# lab_1.net
KiCad netlist of a schematic drawn in EasyEDA
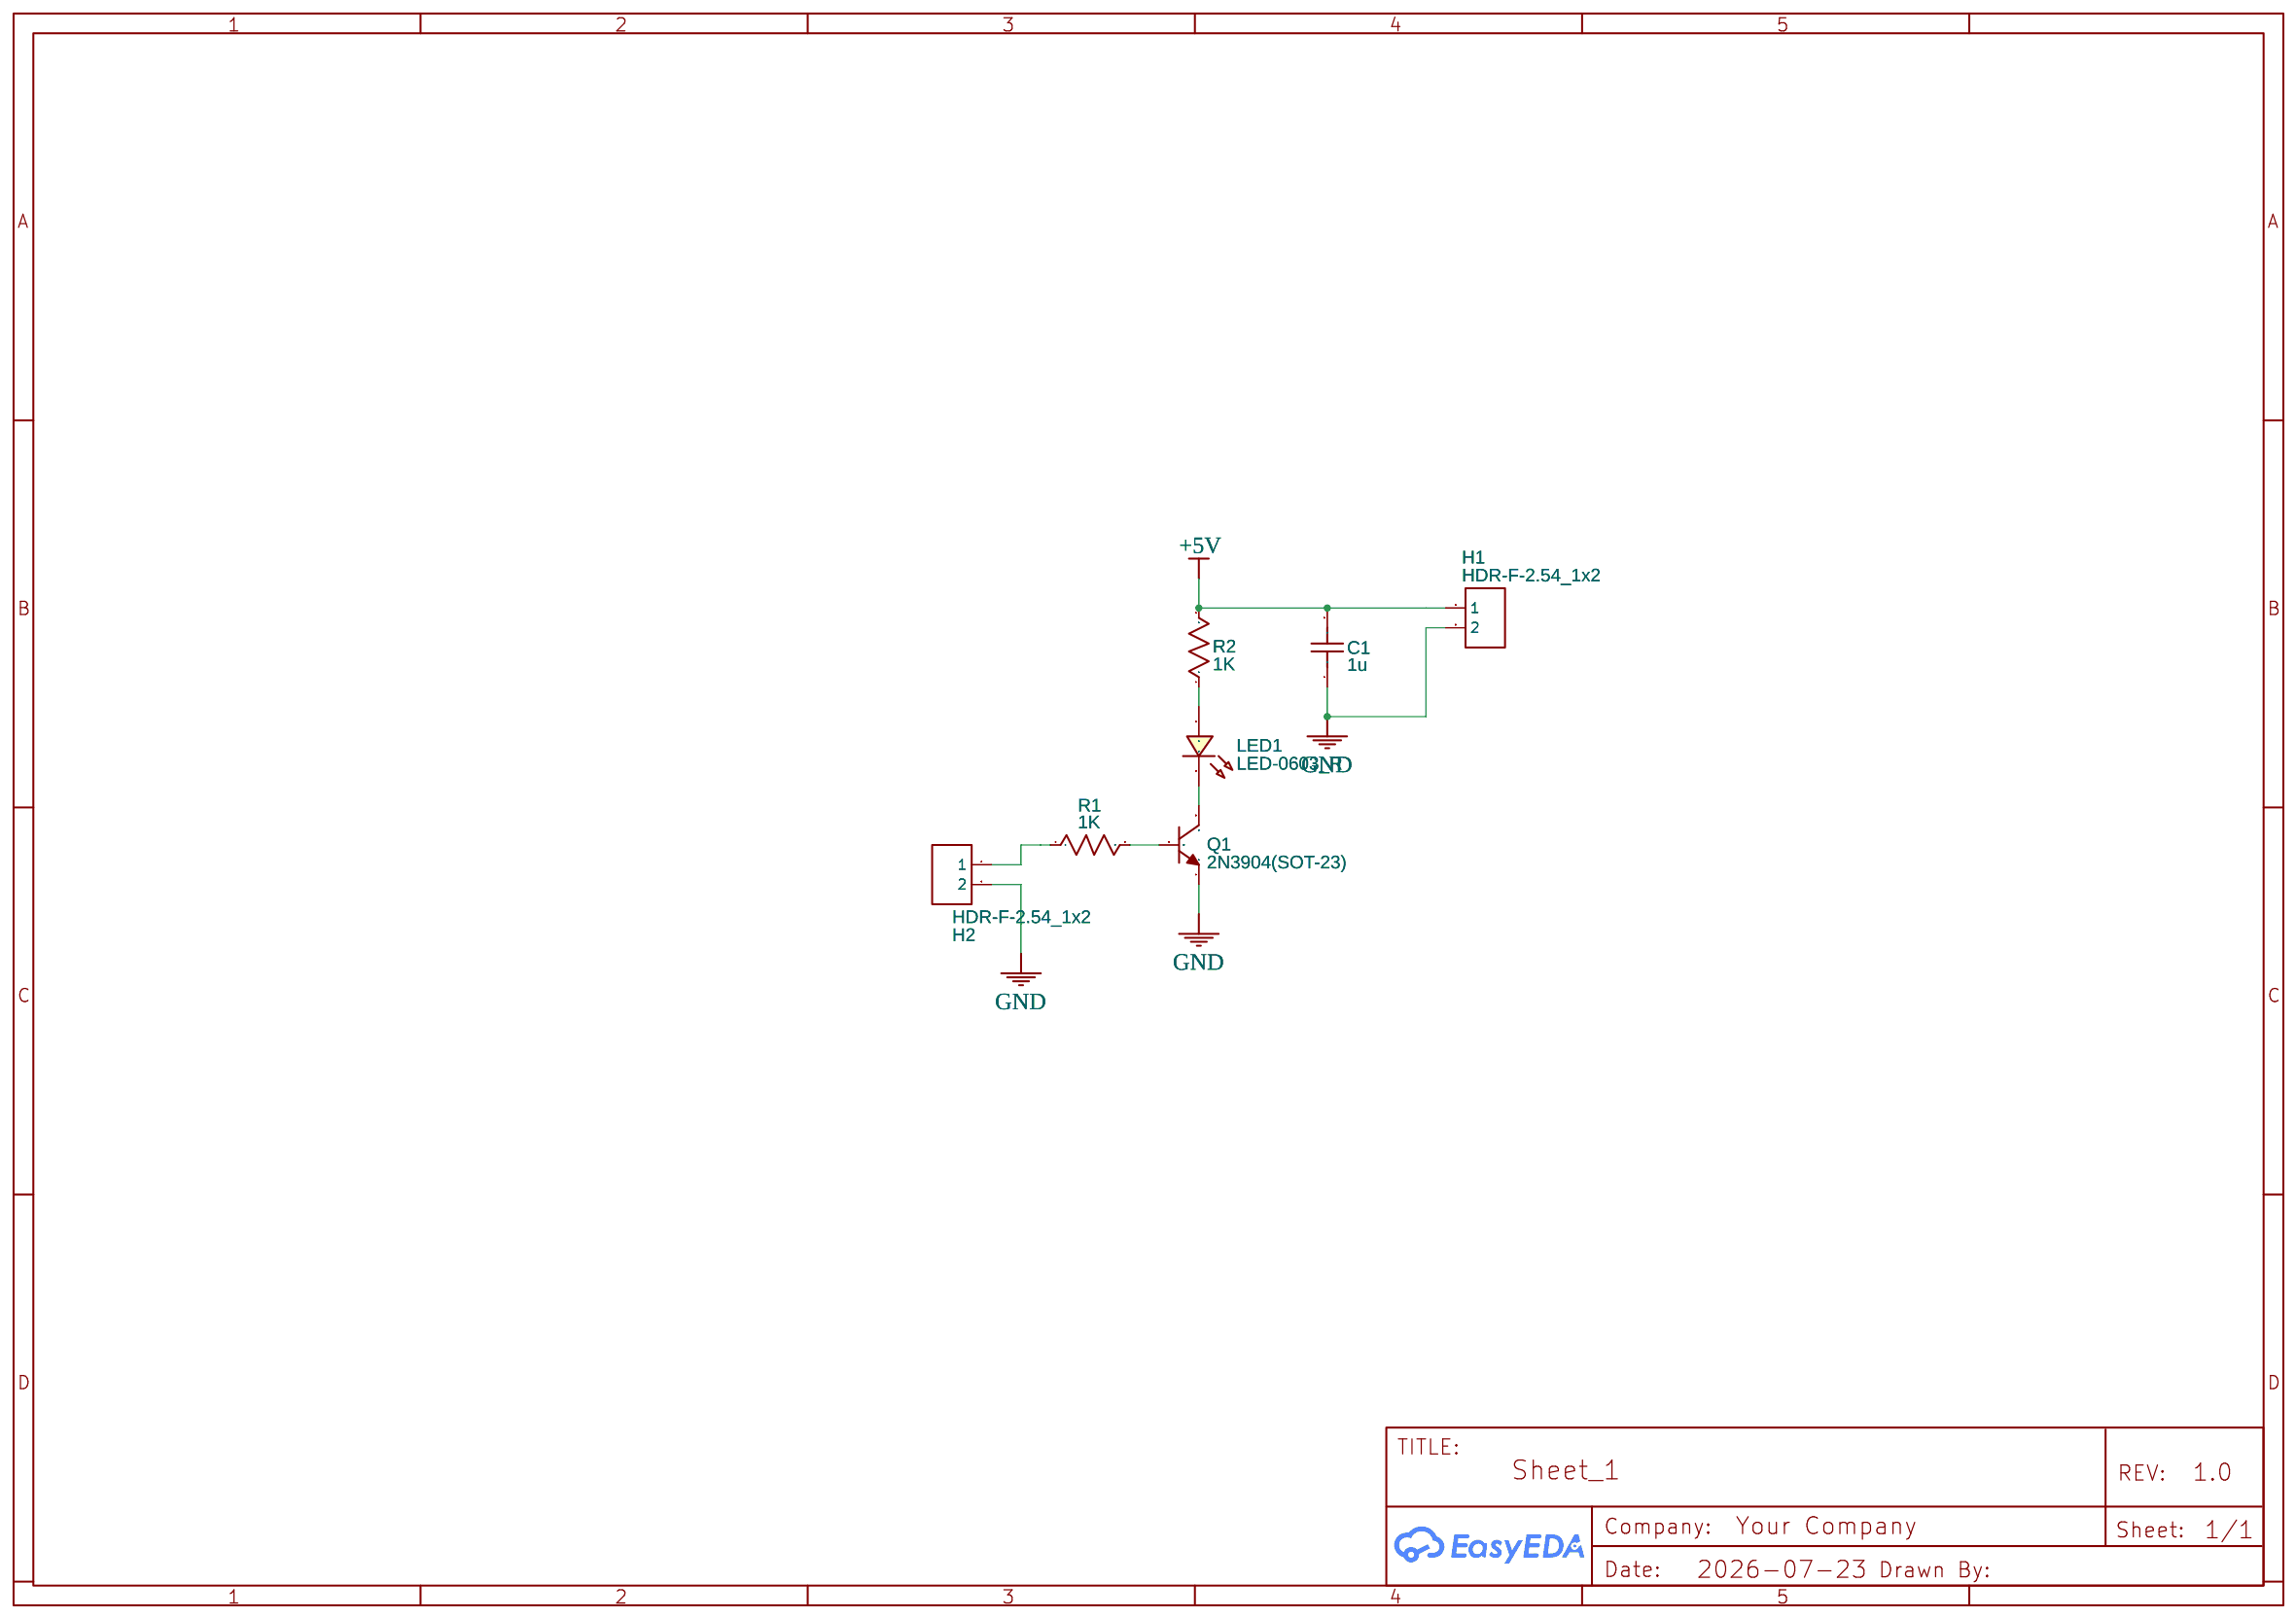
[diagram p0: schematic sheet]

(export (version "E")
  (design (tool "Eeschema 10.0.6"))
  (components
    (comp (ref "C1") (value "1u") (libsource (lib "") (part "Capacitor_US")))
    (comp (ref "H1") (value "HDR-F-2.54_1x2") (libsource (lib "") (part "HDR-F-2.54_1x2")))
    (comp (ref "H2") (value "HDR-F-2.54_1x2") (libsource (lib "") (part "HDR-F-2.54_1x2_1")))
    (comp (ref "LED1")
      (value "LED-0603_R")
      (fields
        (field (name "Manufacturer Part") "19-217/R6C-AL1M2VY/3T")
        (field (name "Manufacturer") "EVERLIGHT(台湾亿光)")
      )
      (libsource (lib "") (part "LED-0603_R"))
    )
    (comp (ref "Q1")
      (value "2N3904(SOT-23)")
      (fields (field (name "Manufacturer Part") "2n3904S-RTK/PS") (field (name "Manufacturer") "KEC"))
      (libsource (lib "") (part "2N3904(SOT-23)"))
    )
    (comp (ref "R1") (value "1K") (libsource (lib "") (part "Resistor_US")))
    (comp (ref "R2") (value "1K") (libsource (lib "") (part "Resistor_US_1")))
  )
  (nets
    (net (code "1") (name "+5V") (class "Default")
      (node (ref "C1") (pin "2") (pinfunction "2_2") (pintype "unspecified"))
      (node (ref "H1") (pin "1") (pinfunction "1_1") (pintype "input"))
      (node (ref "R2") (pin "2") (pinfunction "2_2") (pintype "unspecified"))
    )
    (net (code "2") (name "GND") (class "Default")
      (node (ref "C1") (pin "1") (pinfunction "1_1") (pintype "unspecified"))
      (node (ref "H1") (pin "2") (pinfunction "2_2") (pintype "input"))
      (node (ref "H2") (pin "2") (pinfunction "2_2") (pintype "input"))
      (node (ref "Q1") (pin "1") (pinfunction "E_1") (pintype "input"))
    )
    (net (code "3") (name "Net-(H2-Pad1)") (class "Default")
      (node (ref "H2") (pin "1") (pinfunction "1_1") (pintype "input"))
      (node (ref "R1") (pin "1") (pinfunction "1_1") (pintype "unspecified"))
    )
    (net (code "4") (name "Net-(LED1-Pad1)") (class "Default")
      (node (ref "LED1") (pin "1") (pinfunction "1_1") (pintype "unspecified"))
      (node (ref "R2") (pin "1") (pinfunction "1_1") (pintype "unspecified"))
    )
    (net (code "5") (name "Net-(Q1-B)") (class "Default")
      (node (ref "Q1") (pin "2") (pinfunction "B_2") (pintype "input"))
      (node (ref "R1") (pin "2") (pinfunction "2_2") (pintype "unspecified"))
    )
    (net (code "6") (name "Net-(Q1-C)") (class "Default")
      (node (ref "LED1") (pin "2") (pinfunction "2_2") (pintype "unspecified"))
      (node (ref "Q1") (pin "3") (pinfunction "C_3") (pintype "input"))
    )
  )
)
